# SCH_PS7805.net
KiCad netlist of a schematic drawn in Altium Designer
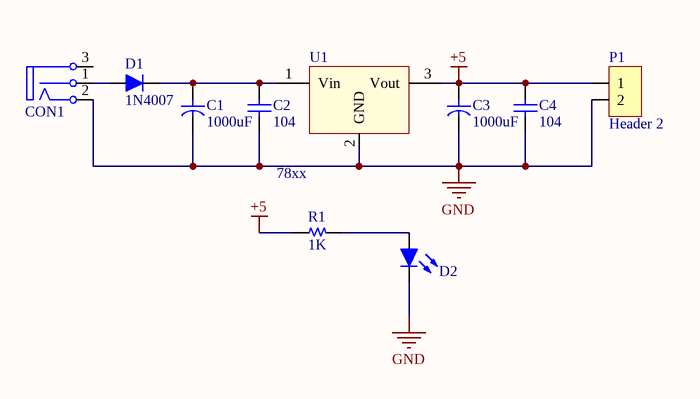
[diagram p0: SCH_PS7805.SchDoc]

(export (version "E")
  (design (tool "Eeschema 10.0.6"))
  (components
    (comp (ref "C1")
      (value "1000uF")
      (footprint "CYL/D.400/LS.200")
      (description "Capacitor pol")
      (libsource (lib "chipfc_libs") (part "Capacitor"))
    )
    (comp (ref "C2")
      (value "104")
      (footprint "CAP Ceramic/W300")
      (description "Capacitor non-pol")
      (libsource (lib "chipfc_libs") (part "Capacitor NP"))
    )
    (comp (ref "C3")
      (value "1000uF")
      (footprint "CYL/D.400/LS.200")
      (description "Capacitor pol")
      (libsource (lib "chipfc_libs") (part "Capacitor"))
    )
    (comp (ref "C4")
      (value "104")
      (footprint "CAP Ceramic/W300")
      (description "Capacitor non-pol")
      (libsource (lib "chipfc_libs") (part "Capacitor NP"))
    )
    (comp (ref "CON1")
      (value "CON DC PWR")
      (footprint "CONN/DC/PWR/5.0MM")
      (description "DC input connector")
      (libsource (lib "connectors") (part "CON DC PWR"))
    )
    (comp (ref "D1")
      (value "1N4007")
      (footprint "DO-41")
      (description "Default Diode")
      (libsource (lib "chipfc_libs") (part "Diode"))
    )
    (comp (ref "D2")
      (value "Led")
      (footprint "LED 3MM - green")
      (description "Typical LED")
      (libsource (lib "led") (part "Led"))
    )
    (comp (ref "P1")
      (value "Header 2")
      (footprint "HDR/Terminal/2")
      (description "Header, 2-Pin")
      (libsource (lib "connectors") (part "Header 2"))
    )
    (comp (ref "R1")
      (value "1K")
      (footprint "R 1/4W/300")
      (description "Resistor")
      (libsource (lib "chipfc_libs") (part "Resistor"))
    )
    (comp (ref "U1")
      (value "78xx")
      (footprint "TO-220")
      (description "LDO Fixed Voltage regulator")
      (libsource (lib "chipfc_libs") (part "78xx"))
    )
  )
  (nets
    (net (code "1") (name "+5") (class "Default")
      (node (ref "C3") (pin "1") (pinfunction "1_1") (pintype "passive"))
      (node (ref "C4") (pin "1") (pinfunction "1_1") (pintype "passive"))
      (node (ref "P1") (pin "1") (pinfunction "1_1") (pintype "passive"))
      (node (ref "R1") (pin "1") (pinfunction "1_1") (pintype "passive"))
      (node (ref "U1") (pin "3") (pinfunction "Vout_3") (pintype "passive"))
    )
    (net (code "2") (name "GND") (class "Default")
      (node (ref "C1") (pin "2") (pinfunction "2_2") (pintype "passive"))
      (node (ref "C2") (pin "2") (pinfunction "2_2") (pintype "passive"))
      (node (ref "C3") (pin "2") (pinfunction "2_2") (pintype "passive"))
      (node (ref "C4") (pin "2") (pinfunction "2_2") (pintype "passive"))
      (node (ref "CON1") (pin "2") (pinfunction "T_2") (pintype "passive"))
      (node (ref "D2") (pin "2") (pinfunction "K_2") (pintype "passive"))
      (node (ref "P1") (pin "2") (pinfunction "2_2") (pintype "passive"))
      (node (ref "U1") (pin "2") (pinfunction "GND_2") (pintype "passive"))
    )
    (net (code "3") (name "Net-(CON1-S)") (class "Default")
      (node (ref "CON1") (pin "1") (pinfunction "S_1") (pintype "power_in"))
      (node (ref "D1") (pin "1") (pinfunction "A_1") (pintype "passive"))
    )
    (net (code "4") (name "Net-(D1-K)") (class "Default")
      (node (ref "C1") (pin "1") (pinfunction "1_1") (pintype "passive"))
      (node (ref "C2") (pin "1") (pinfunction "1_1") (pintype "passive"))
      (node (ref "D1") (pin "2") (pinfunction "K_2") (pintype "passive"))
      (node (ref "U1") (pin "1") (pinfunction "Vin_1") (pintype "power_in"))
    )
    (net (code "5") (name "Net-(D2-A)") (class "Default")
      (node (ref "D2") (pin "1") (pinfunction "A_1") (pintype "passive"))
      (node (ref "R1") (pin "2") (pinfunction "2_2") (pintype "passive"))
    )
    (net (code "6") (name "unconnected-(CON1-TN-Pad3)") (class "Default")
      (node (ref "CON1") (pin "3") (pinfunction "TN_3") (pintype "passive"))
    )
  )
)
